# M_D_ext_power-gv.net
KiCad netlist of a schematic drawn in EAGLE
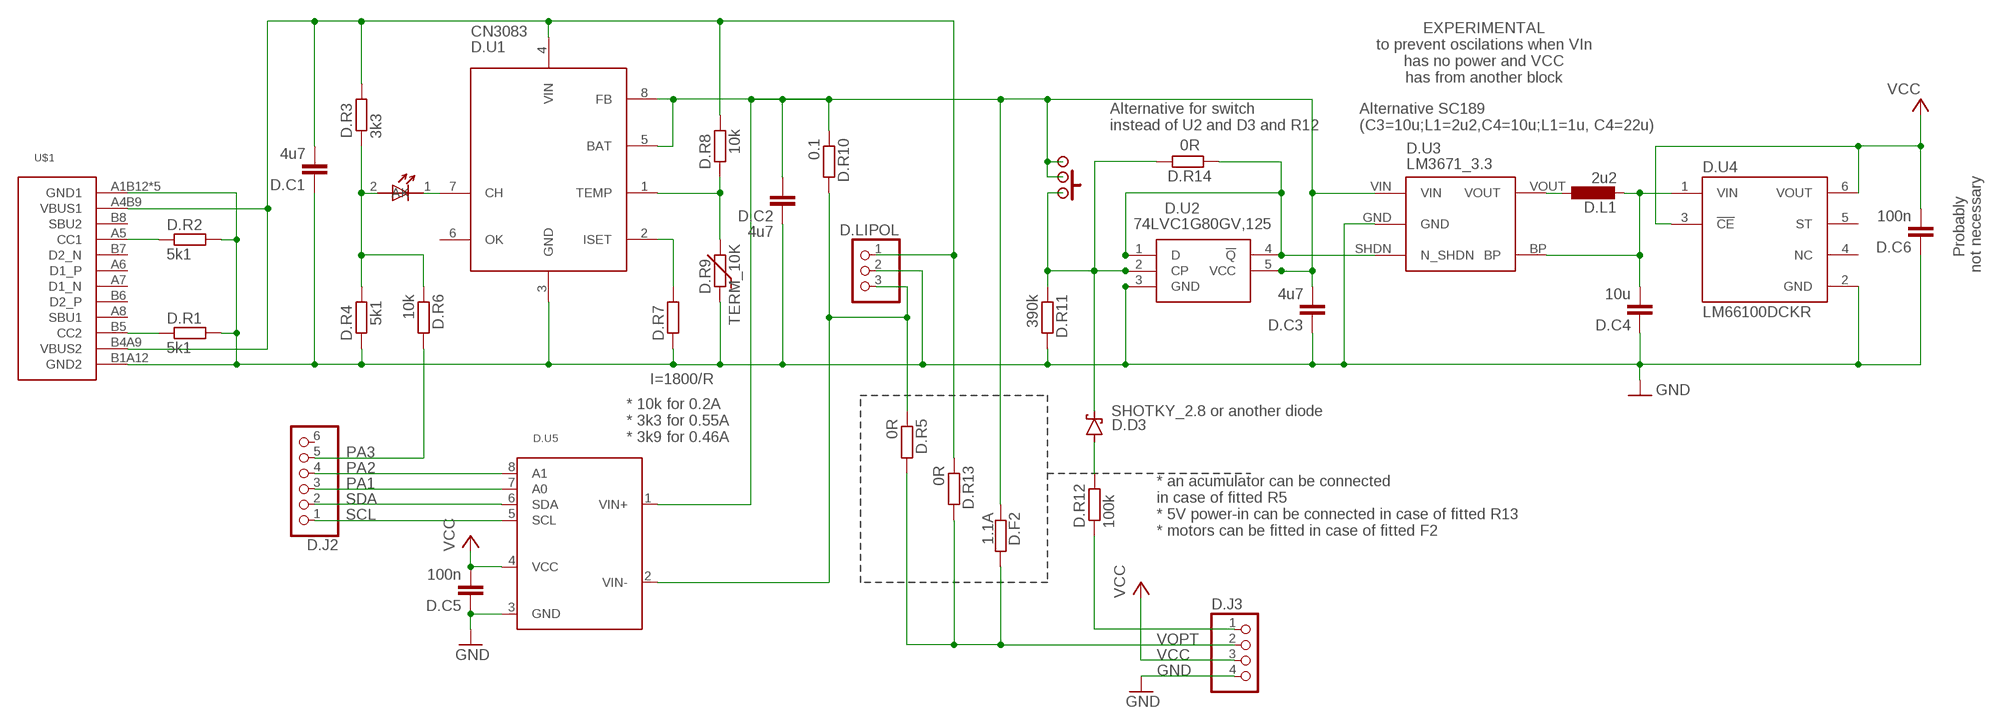
[diagram p0: schematic, sheet 1]

(export (version "E")
  (design (tool "Eeschema 10.0.6"))
  (components
    (comp (ref "D.C1")
      (value "4u7")
      (footprint "eagle-import:C0603")
      (libsource (lib "eagle-import") (part "C-EUC0603"))
    )
    (comp (ref "D.C2")
      (value "4u7")
      (footprint "eagle-import:C0603")
      (libsource (lib "eagle-import") (part "C-EUC0603"))
    )
    (comp (ref "D.C3")
      (value "4u7")
      (footprint "eagle-import:C0603")
      (libsource (lib "eagle-import") (part "C-EUC0603"))
    )
    (comp (ref "D.C4")
      (value "10u")
      (footprint "eagle-import:C0603")
      (libsource (lib "eagle-import") (part "C-EUC0603"))
    )
    (comp (ref "D.C5")
      (value "100n")
      (footprint "eagle-import:C0603")
      (libsource (lib "eagle-import") (part "C-EUC0603"))
    )
    (comp (ref "D.C6")
      (value "100n")
      (footprint "eagle-import:C0603")
      (libsource (lib "eagle-import") (part "C-EUC0603"))
    )
    (comp (ref "D.D1")
      (value "LED_1.8")
      (footprint "eagle-import:LED_1.8")
      (libsource (lib "eagle-import") (part "LED_1.8"))
    )
    (comp (ref "D.D3")
      (value "SHOTKY_2.8 or another diode")
      (footprint "eagle-import:SHOTKY_2.8")
      (libsource (lib "eagle-import") (part "SHOTKY_2.8"))
    )
    (comp (ref "D.F2")
      (value "1.1A")
      (footprint "eagle-import:R0805")
      (libsource (lib "eagle-import") (part "R-EU_R0805"))
    )
    (comp (ref "D.J2")
      (value "PINHD-1X6")
      (footprint "eagle-import:1X06")
      (libsource (lib "eagle-import") (part "PINHD-1X6"))
    )
    (comp (ref "D.J3")
      (value "PINHD-1X4")
      (footprint "eagle-import:1X04")
      (libsource (lib "eagle-import") (part "PINHD-1X4"))
    )
    (comp (ref "D.L1")
      (value "2u2")
      (footprint "eagle-import:L3230M")
      (libsource (lib "eagle-import") (part "L-EUL3230M"))
    )
    (comp (ref "D.LIPOL")
      (value "PINHEAD-1X3-2")
      (footprint "eagle-import:1X-03-2")
      (libsource (lib "eagle-import") (part "PINHEAD-1X3-2"))
    )
    (comp (ref "D.ON/OFF/RESET")
      (value "SWITCH")
      (footprint "eagle-import:SWITCH")
      (libsource (lib "eagle-import") (part "SWITCH"))
    )
    (comp (ref "D.R1")
      (value "5k1")
      (footprint "eagle-import:R0603")
      (libsource (lib "eagle-import") (part "R-EU_R0603"))
    )
    (comp (ref "D.R2")
      (value "5k1")
      (footprint "eagle-import:R0603")
      (libsource (lib "eagle-import") (part "R-EU_R0603"))
    )
    (comp (ref "D.R3")
      (value "3k3")
      (footprint "eagle-import:R0603")
      (libsource (lib "eagle-import") (part "R-EU_R0603"))
    )
    (comp (ref "D.R4")
      (value "5k1")
      (footprint "eagle-import:R0603")
      (libsource (lib "eagle-import") (part "R-EU_R0603"))
    )
    (comp (ref "D.R5")
      (value "0R")
      (footprint "eagle-import:R0603")
      (libsource (lib "eagle-import") (part "R-EU_R0603"))
    )
    (comp (ref "D.R6")
      (value "10k")
      (footprint "eagle-import:R0603")
      (libsource (lib "eagle-import") (part "R-EU_R0603"))
    )
    (comp (ref "D.R7")
      (value "I=1800/R")
      (footprint "eagle-import:R0603")
      (libsource (lib "eagle-import") (part "R-EU_R0603"))
    )
    (comp (ref "D.R8")
      (value "10k")
      (footprint "eagle-import:R0603")
      (libsource (lib "eagle-import") (part "R-EU_R0603"))
    )
    (comp (ref "D.R9")
      (value "TERM_10K")
      (footprint "eagle-import:THERM")
      (libsource (lib "eagle-import") (part "THERM"))
    )
    (comp (ref "D.R10")
      (value "0.1")
      (footprint "eagle-import:R0805")
      (libsource (lib "eagle-import") (part "R-EU_R0805"))
    )
    (comp (ref "D.R11")
      (value "390k")
      (footprint "eagle-import:R0603")
      (libsource (lib "eagle-import") (part "R-EU_R0603"))
    )
    (comp (ref "D.R12")
      (value "100k")
      (footprint "eagle-import:R0603")
      (libsource (lib "eagle-import") (part "R-EU_R0603"))
    )
    (comp (ref "D.R13")
      (value "0R")
      (footprint "eagle-import:R0603")
      (libsource (lib "eagle-import") (part "R-EU_R0603"))
    )
    (comp (ref "D.R14")
      (value "0R")
      (footprint "eagle-import:R0603")
      (libsource (lib "eagle-import") (part "R-EU_R0603"))
    )
    (comp (ref "D.U1")
      (value "CN3083")
      (footprint "eagle-import:SOP8")
      (libsource (lib "eagle-import") (part "CN3083"))
    )
    (comp (ref "D.U2")
      (value "74LVC1G80GV,125")
      (footprint "eagle-import:SOT95P275X110-5N")
      (libsource (lib "eagle-import") (part "74LVC1G80GV,125"))
    )
    (comp (ref "D.U3")
      (value "LM3671_3.3")
      (footprint "eagle-import:SOT32-5")
      (libsource (lib "eagle-import") (part "STABILISER_APE8865"))
    )
    (comp (ref "D.U4")
      (value "LM66100DCKR")
      (footprint "eagle-import:SOT65P210X110-6N")
      (fields (field (name "MF") "Texas Instruments"))
      (libsource (lib "eagle-import") (part "LM66100DCKR"))
    )
    (comp (ref "D.U5")
      (value "INA219")
      (footprint "eagle-import:SOT23-8")
      (libsource (lib "eagle-import") (part "INA219"))
    )
    (comp (ref "U$1")
      (value "USB-C")
      (footprint "eagle-import:USB-C")
      (libsource (lib "eagle-import") (part "USB-C"))
    )
  )
  (nets
    (net (code "1") (name "/PA1") (class "Default")
      (node (ref "D.J2") (pin "3") (pinfunction "3_3") (pintype "passive"))
      (node (ref "D.U5") (pin "7") (pinfunction "A0_7") (pintype "bidirectional"))
    )
    (net (code "2") (name "/PA2") (class "Default")
      (node (ref "D.J2") (pin "4") (pinfunction "4_4") (pintype "passive"))
      (node (ref "D.U5") (pin "8") (pinfunction "A1_8") (pintype "bidirectional"))
    )
    (net (code "3") (name "/PA3") (class "Default")
      (node (ref "D.J2") (pin "5") (pinfunction "5_5") (pintype "passive"))
      (node (ref "D.R6") (pin "2") (pinfunction "2_2") (pintype "passive"))
    )
    (net (code "4") (name "/SCL") (class "Default")
      (node (ref "D.J2") (pin "1") (pinfunction "1_1") (pintype "passive"))
      (node (ref "D.U5") (pin "5") (pinfunction "SCL_5") (pintype "bidirectional"))
    )
    (net (code "5") (name "/SDA") (class "Default")
      (node (ref "D.J2") (pin "2") (pinfunction "2_2") (pintype "passive"))
      (node (ref "D.U5") (pin "6") (pinfunction "SDA_6") (pintype "bidirectional"))
    )
    (net (code "6") (name "/VOPT") (class "Default")
      (node (ref "D.F2") (pin "2") (pinfunction "2_2") (pintype "passive"))
      (node (ref "D.J3") (pin "2") (pinfunction "2_2") (pintype "passive"))
      (node (ref "D.R13") (pin "2") (pinfunction "2_2") (pintype "passive"))
      (node (ref "D.R5") (pin "2") (pinfunction "2_2") (pintype "passive"))
    )
    (net (code "7") (name "GND") (class "Default")
      (node (ref "D.C1") (pin "1") (pinfunction "1_1") (pintype "passive"))
      (node (ref "D.C2") (pin "1") (pinfunction "1_1") (pintype "passive"))
      (node (ref "D.C3") (pin "1") (pinfunction "1_1") (pintype "passive"))
      (node (ref "D.C4") (pin "1") (pinfunction "1_1") (pintype "passive"))
      (node (ref "D.C5") (pin "1") (pinfunction "1_1") (pintype "passive"))
      (node (ref "D.C6") (pin "1") (pinfunction "1_1") (pintype "passive"))
      (node (ref "D.J3") (pin "4") (pinfunction "4_4") (pintype "passive"))
      (node (ref "D.LIPOL") (pin "2") (pinfunction "2_2") (pintype "passive"))
      (node (ref "D.R1") (pin "2") (pinfunction "2_2") (pintype "passive"))
      (node (ref "D.R11") (pin "2") (pinfunction "2_2") (pintype "passive"))
      (node (ref "D.R2") (pin "2") (pinfunction "2_2") (pintype "passive"))
      (node (ref "D.R4") (pin "1") (pinfunction "1_1") (pintype "passive"))
      (node (ref "D.R7") (pin "1") (pinfunction "1_1") (pintype "passive"))
      (node (ref "D.R9") (pin "1") (pinfunction "1_1") (pintype "passive"))
      (node (ref "D.U1") (pin "3") (pinfunction "GND_3") (pintype "bidirectional"))
      (node (ref "D.U2") (pin "3") (pinfunction "GND_3") (pintype "bidirectional"))
      (node (ref "D.U3") (pin "GND") (pinfunction "GND_GND") (pintype "bidirectional"))
      (node (ref "D.U4") (pin "2") (pinfunction "GND_2") (pintype "power_in"))
      (node (ref "D.U5") (pin "3") (pinfunction "GND_3") (pintype "bidirectional"))
      (node (ref "U$1") (pin "A1B12") (pinfunction "GND1_A1B12") (pintype "bidirectional"))
      (node (ref "U$1") (pin "B1A12") (pinfunction "GND2_B1A12") (pintype "bidirectional"))
      (node (ref "U$1") (pin "SH1") (pinfunction "GND1_SH1") (pintype "bidirectional"))
      (node (ref "U$1") (pin "SH2") (pinfunction "GND1_SH2") (pintype "bidirectional"))
      (node (ref "U$1") (pin "SH3") (pinfunction "GND1_SH3") (pintype "bidirectional"))
      (node (ref "U$1") (pin "SH4") (pinfunction "GND1_SH4") (pintype "bidirectional"))
    )
    (net (code "8") (name "Net-(D.D1-A)") (class "Default")
      (node (ref "D.D1") (pin "2") (pinfunction "A_2") (pintype "bidirectional"))
      (node (ref "D.R3") (pin "1") (pinfunction "1_1") (pintype "passive"))
      (node (ref "D.R4") (pin "2") (pinfunction "2_2") (pintype "passive"))
      (node (ref "D.R6") (pin "1") (pinfunction "1_1") (pintype "passive"))
    )
    (net (code "9") (name "Net-(D.D1-K)") (class "Default")
      (node (ref "D.D1") (pin "1") (pinfunction "K_1") (pintype "bidirectional"))
      (node (ref "D.U1") (pin "7") (pinfunction "CH_7") (pintype "bidirectional"))
    )
    (net (code "10") (name "Net-(D.D3-C)") (class "Default")
      (node (ref "D.D3") (pin "K") (pinfunction "C_K") (pintype "passive"))
      (node (ref "D.ON/OFF/RESET") (pin "P$1") (pinfunction "P$1_P$1") (pintype "bidirectional"))
      (node (ref "D.ON/OFF/RESET") (pin "P$5") (pinfunction "P$1_P$5") (pintype "bidirectional"))
      (node (ref "D.ON/OFF/RESET") (pin "P$7") (pinfunction "P$1_P$7") (pintype "bidirectional"))
      (node (ref "D.R11") (pin "1") (pinfunction "1_1") (pintype "passive"))
      (node (ref "D.R14") (pin "2") (pinfunction "2_2") (pintype "passive"))
      (node (ref "D.U2") (pin "2") (pinfunction "CP_2") (pintype "bidirectional"))
    )
    (net (code "11") (name "Net-(D.D3-PadA)") (class "Default")
      (node (ref "D.D3") (pin "A") (pinfunction "A_A") (pintype "passive"))
      (node (ref "D.R12") (pin "2") (pinfunction "2_2") (pintype "passive"))
    )
    (net (code "12") (name "Net-(D.J3-Pad1)") (class "Default")
      (node (ref "D.J3") (pin "1") (pinfunction "1_1") (pintype "passive"))
      (node (ref "D.R12") (pin "1") (pinfunction "1_1") (pintype "passive"))
    )
    (net (code "13") (name "Net-(D.L1-Pad1)") (class "Default")
      (node (ref "D.L1") (pin "1") (pinfunction "1_1") (pintype "passive"))
      (node (ref "D.U3") (pin "VOUT") (pinfunction "VOUT_VOUT") (pintype "bidirectional"))
    )
    (net (code "14") (name "Net-(D.U1-BAT)") (class "Default")
      (node (ref "D.C2") (pin "2") (pinfunction "2_2") (pintype "passive"))
      (node (ref "D.C3") (pin "2") (pinfunction "2_2") (pintype "passive"))
      (node (ref "D.F2") (pin "1") (pinfunction "1_1") (pintype "passive"))
      (node (ref "D.ON/OFF/RESET") (pin "P$2") (pinfunction "P$2_P$2") (pintype "bidirectional"))
      (node (ref "D.ON/OFF/RESET") (pin "P$3") (pinfunction "P$3_P$3") (pintype "bidirectional"))
      (node (ref "D.ON/OFF/RESET") (pin "P$4") (pinfunction "P$3_P$4") (pintype "bidirectional"))
      (node (ref "D.ON/OFF/RESET") (pin "P$6") (pinfunction "P$3_P$6") (pintype "bidirectional"))
      (node (ref "D.R10") (pin "1") (pinfunction "1_1") (pintype "passive"))
      (node (ref "D.U1") (pin "5") (pinfunction "BAT_5") (pintype "bidirectional"))
      (node (ref "D.U1") (pin "8") (pinfunction "FB_8") (pintype "bidirectional"))
      (node (ref "D.U2") (pin "5") (pinfunction "VCC_5") (pintype "bidirectional"))
      (node (ref "D.U3") (pin "VIN") (pinfunction "VIN_VIN") (pintype "bidirectional"))
      (node (ref "D.U5") (pin "1") (pinfunction "VIN+_1") (pintype "bidirectional"))
    )
    (net (code "15") (name "Net-(D.U1-ISET)") (class "Default")
      (node (ref "D.R7") (pin "2") (pinfunction "2_2") (pintype "passive"))
      (node (ref "D.U1") (pin "2") (pinfunction "ISET_2") (pintype "bidirectional"))
    )
    (net (code "16") (name "Net-(D.U1-TEMP)") (class "Default")
      (node (ref "D.R8") (pin "1") (pinfunction "1_1") (pintype "passive"))
      (node (ref "D.R9") (pin "2") (pinfunction "2_2") (pintype "passive"))
      (node (ref "D.U1") (pin "1") (pinfunction "TEMP_1") (pintype "bidirectional"))
    )
    (net (code "17") (name "Net-(D.U1-VIN)") (class "Default")
      (node (ref "D.C1") (pin "2") (pinfunction "2_2") (pintype "passive"))
      (node (ref "D.LIPOL") (pin "1") (pinfunction "1_1") (pintype "passive"))
      (node (ref "D.R13") (pin "1") (pinfunction "1_1") (pintype "passive"))
      (node (ref "D.R3") (pin "2") (pinfunction "2_2") (pintype "passive"))
      (node (ref "D.R8") (pin "2") (pinfunction "2_2") (pintype "passive"))
      (node (ref "D.U1") (pin "4") (pinfunction "VIN_4") (pintype "bidirectional"))
      (node (ref "U$1") (pin "A4B9") (pinfunction "VBUS1_A4B9") (pintype "bidirectional"))
      (node (ref "U$1") (pin "B4A9") (pinfunction "VBUS2_B4A9") (pintype "bidirectional"))
    )
    (net (code "18") (name "Net-(D.U2-D)") (class "Default")
      (node (ref "D.R14") (pin "1") (pinfunction "1_1") (pintype "passive"))
      (node (ref "D.U2") (pin "1") (pinfunction "D_1") (pintype "bidirectional"))
      (node (ref "D.U2") (pin "4") (pinfunction "~{Q}_4") (pintype "bidirectional"))
      (node (ref "D.U3") (pin "SHDN") (pinfunction "N_SHDN_SHDN") (pintype "bidirectional"))
    )
    (net (code "19") (name "Net-(D.U4-VIN)") (class "Default")
      (node (ref "D.C4") (pin "2") (pinfunction "2_2") (pintype "passive"))
      (node (ref "D.L1") (pin "2") (pinfunction "2_2") (pintype "passive"))
      (node (ref "D.U3") (pin "BP") (pinfunction "BP_BP") (pintype "bidirectional"))
      (node (ref "D.U4") (pin "1") (pinfunction "VIN_1") (pintype "input"))
    )
    (net (code "20") (name "Net-(D.U5-VIN-)") (class "Default")
      (node (ref "D.LIPOL") (pin "3") (pinfunction "3_3") (pintype "passive"))
      (node (ref "D.R10") (pin "2") (pinfunction "2_2") (pintype "passive"))
      (node (ref "D.R5") (pin "1") (pinfunction "1_1") (pintype "passive"))
      (node (ref "D.U5") (pin "2") (pinfunction "VIN-_2") (pintype "bidirectional"))
    )
    (net (code "21") (name "Net-(U$1-CC1)") (class "Default")
      (node (ref "D.R2") (pin "1") (pinfunction "1_1") (pintype "passive"))
      (node (ref "U$1") (pin "A5") (pinfunction "CC1_A5") (pintype "bidirectional"))
    )
    (net (code "22") (name "Net-(U$1-CC2)") (class "Default")
      (node (ref "D.R1") (pin "1") (pinfunction "1_1") (pintype "passive"))
      (node (ref "U$1") (pin "B5") (pinfunction "CC2_B5") (pintype "bidirectional"))
    )
    (net (code "23") (name "VCC") (class "Default")
      (node (ref "D.C5") (pin "2") (pinfunction "2_2") (pintype "passive"))
      (node (ref "D.C6") (pin "2") (pinfunction "2_2") (pintype "passive"))
      (node (ref "D.J3") (pin "3") (pinfunction "3_3") (pintype "passive"))
      (node (ref "D.U4") (pin "3") (pinfunction "~{CE}_3") (pintype "input"))
      (node (ref "D.U4") (pin "6") (pinfunction "VOUT_6") (pintype "output"))
      (node (ref "D.U5") (pin "4") (pinfunction "VCC_4") (pintype "bidirectional"))
    )
    (net (code "24") (name "unconnected-(D.J2-Pad6)") (class "Default")
      (node (ref "D.J2") (pin "6") (pinfunction "6_6") (pintype "passive"))
    )
    (net (code "25") (name "unconnected-(D.U1-OK-Pad6)") (class "Default")
      (node (ref "D.U1") (pin "6") (pinfunction "OK_6") (pintype "bidirectional"))
    )
    (net (code "26") (name "unconnected-(D.U4-NC-Pad4)") (class "Default")
      (node (ref "D.U4") (pin "4") (pinfunction "NC_4") (pintype "no_connect"))
    )
    (net (code "27") (name "unconnected-(D.U4-ST-Pad5)") (class "Default")
      (node (ref "D.U4") (pin "5") (pinfunction "ST_5") (pintype "output"))
    )
    (net (code "28") (name "unconnected-(U$1-D1_N-PadA7)") (class "Default")
      (node (ref "U$1") (pin "A7") (pinfunction "D1_N_A7") (pintype "bidirectional"))
    )
    (net (code "29") (name "unconnected-(U$1-D1_P-PadA6)") (class "Default")
      (node (ref "U$1") (pin "A6") (pinfunction "D1_P_A6") (pintype "bidirectional"))
    )
    (net (code "30") (name "unconnected-(U$1-D2_N-PadB7)") (class "Default")
      (node (ref "U$1") (pin "B7") (pinfunction "D2_N_B7") (pintype "bidirectional"))
    )
    (net (code "31") (name "unconnected-(U$1-D2_P-PadB6)") (class "Default")
      (node (ref "U$1") (pin "B6") (pinfunction "D2_P_B6") (pintype "bidirectional"))
    )
    (net (code "32") (name "unconnected-(U$1-SBU1-PadA8)") (class "Default")
      (node (ref "U$1") (pin "A8") (pinfunction "SBU1_A8") (pintype "bidirectional"))
    )
    (net (code "33") (name "unconnected-(U$1-SBU2-PadB8)") (class "Default")
      (node (ref "U$1") (pin "B8") (pinfunction "SBU2_B8") (pintype "bidirectional"))
    )
  )
)
